# klaboard_schema.net
KiCad netlist of a schematic drawn in EAGLE
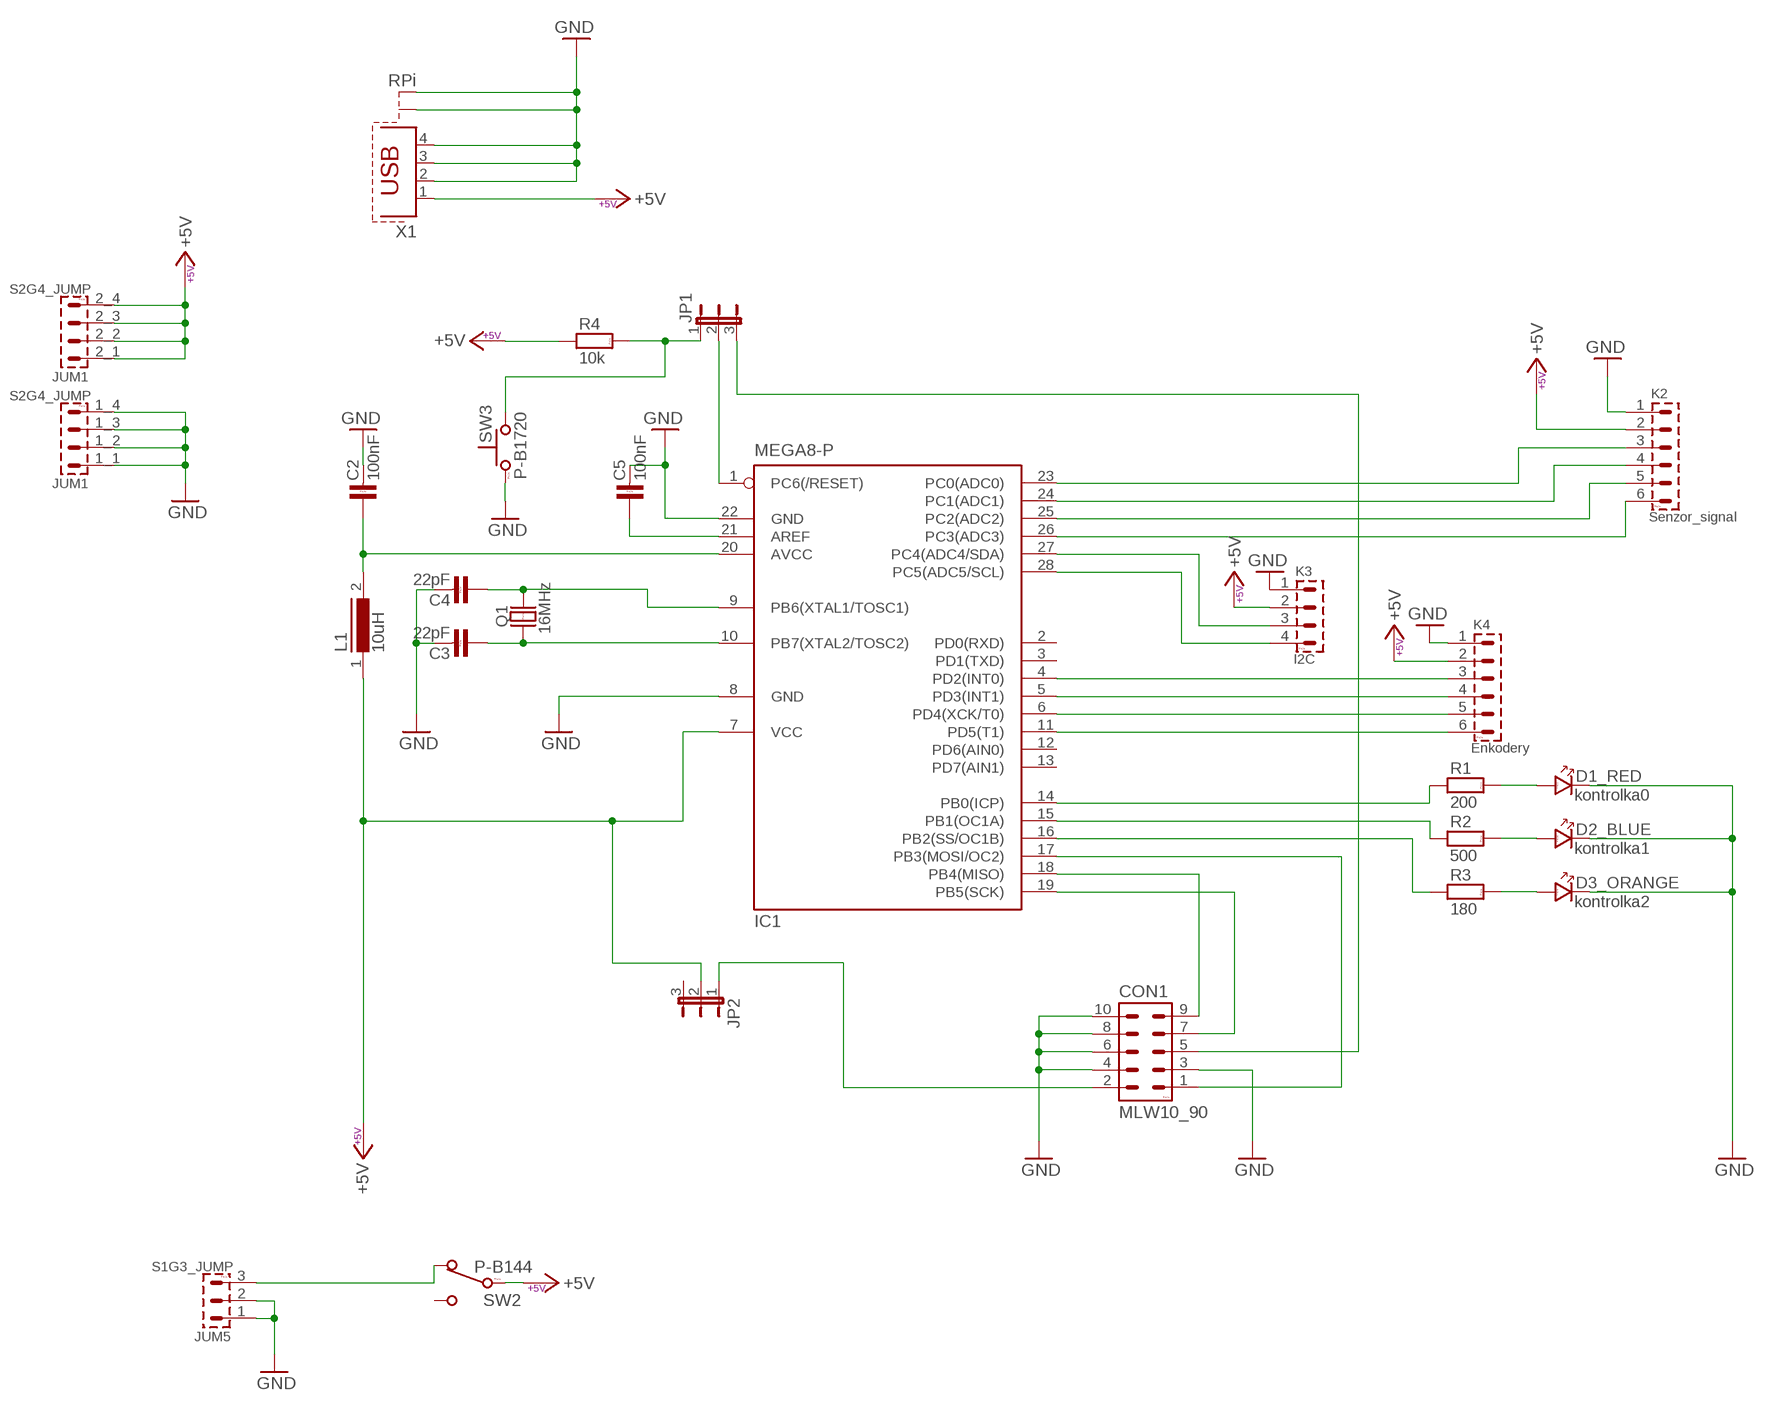
[diagram p0: schematic, sheet 1]

(export (version "E")
  (design (tool "Eeschema 10.0.6"))
  (components
    (comp (ref "C2")
      (value "100nF")
      (footprint "eagle-import:C-7,5")
      (libsource (lib "eagle-import") (part "C-KER_7,5"))
    )
    (comp (ref "C3")
      (value "22pF")
      (footprint "eagle-import:C-7,5")
      (libsource (lib "eagle-import") (part "C-KER_7,5"))
    )
    (comp (ref "C4")
      (value "22pF")
      (footprint "eagle-import:C-7,5")
      (libsource (lib "eagle-import") (part "C-KER_7,5"))
    )
    (comp (ref "C5")
      (value "100nF")
      (footprint "eagle-import:C-7,5")
      (libsource (lib "eagle-import") (part "C-KER_7,5"))
    )
    (comp (ref "CON1")
      (value "MLW10_90")
      (footprint "eagle-import:MLW10A")
      (libsource (lib "eagle-import") (part "MLW10_90°"))
    )
    (comp (ref "D1_RED")
      (value "kontrolka0")
      (footprint "eagle-import:LED_3")
      (libsource (lib "eagle-import") (part "LED_3"))
    )
    (comp (ref "D2_BLUE")
      (value "kontrolka1")
      (footprint "eagle-import:LED_3")
      (libsource (lib "eagle-import") (part "LED_3"))
    )
    (comp (ref "D3_ORANGE")
      (value "kontrolka2")
      (footprint "eagle-import:LED_3")
      (libsource (lib "eagle-import") (part "LED_3"))
    )
    (comp (ref "IC1")
      (value "MEGA8-P")
      (footprint "eagle-import:DIL28-3")
      (libsource (lib "eagle-import") (part "MEGA8-P"))
    )
    (comp (ref "JP1")
      (value "JP2E")
      (footprint "eagle-import:JP2")
      (libsource (lib "eagle-import") (part "JP2E"))
    )
    (comp (ref "JP2")
      (value "JP2E")
      (footprint "eagle-import:JP2")
      (libsource (lib "eagle-import") (part "JP2E"))
    )
    (comp (ref "JUM1")
      (value "S2G4_JUMP")
      (footprint "eagle-import:S2G4_JUM")
      (libsource (lib "eagle-import") (part "S2G4_JUMP"))
    )
    (comp (ref "JUM5")
      (value "S1G3_JUMP")
      (footprint "eagle-import:S1G3_JUM")
      (libsource (lib "eagle-import") (part "S1G3_JUMP"))
    )
    (comp (ref "K2")
      (value "Senzor_signal")
      (footprint "eagle-import:PSH02-06W")
      (libsource (lib "eagle-import") (part "PSH02-06W"))
    )
    (comp (ref "K3")
      (value "I2C")
      (footprint "eagle-import:PSH02-04W")
      (libsource (lib "eagle-import") (part "PSH02-04W"))
    )
    (comp (ref "K4")
      (value "Enkodery")
      (footprint "eagle-import:PSH02-06W")
      (libsource (lib "eagle-import") (part "PSH02-06W"))
    )
    (comp (ref "L1")
      (value "10uH")
      (footprint "eagle-import:SBC10")
      (libsource (lib "eagle-import") (part "SBC10"))
    )
    (comp (ref "Q1")
      (value "16MHz")
      (footprint "eagle-import:HC-49U")
      (libsource (lib "eagle-import") (part "Q_HC-49U"))
    )
    (comp (ref "R1")
      (value "200")
      (footprint "eagle-import:R-12,7")
      (libsource (lib "eagle-import") (part "R_12,7"))
    )
    (comp (ref "R2")
      (value "500")
      (footprint "eagle-import:R-12,7")
      (libsource (lib "eagle-import") (part "R_12,7"))
    )
    (comp (ref "R3")
      (value "180")
      (footprint "eagle-import:R-12,7")
      (libsource (lib "eagle-import") (part "R_12,7"))
    )
    (comp (ref "R4")
      (value "10k")
      (footprint "eagle-import:R-12,7")
      (libsource (lib "eagle-import") (part "R_12,7"))
    )
    (comp (ref "SW2")
      (value "P-B144")
      (footprint "eagle-import:P-B144")
      (libsource (lib "eagle-import") (part "P-B144"))
    )
    (comp (ref "SW3")
      (value "P-B1720")
      (footprint "eagle-import:P-B1720")
      (libsource (lib "eagle-import") (part "P-B1720"))
    )
    (comp (ref "X1")
      (value "RPi")
      (footprint "eagle-import:PN61729-S")
      (libsource (lib "eagle-import") (part "PN61729-S"))
    )
  )
  (nets
    (net (code "1") (name "+5V") (class "Default")
      (node (ref "IC1") (pin "7") (pinfunction "VCC_7") (pintype "power_in"))
      (node (ref "JP2") (pin "2") (pinfunction "2_2") (pintype "passive"))
      (node (ref "JUM1") (pin "2_1") (pinfunction "1_2_1") (pintype "passive"))
      (node (ref "JUM1") (pin "2_2") (pinfunction "2_2_2") (pintype "passive"))
      (node (ref "JUM1") (pin "2_3") (pinfunction "3_2_3") (pintype "passive"))
      (node (ref "JUM1") (pin "2_4") (pinfunction "4_2_4") (pintype "passive"))
      (node (ref "K2") (pin "2") (pinfunction "2_2") (pintype "passive"))
      (node (ref "K3") (pin "2") (pinfunction "2_2") (pintype "passive"))
      (node (ref "K4") (pin "2") (pinfunction "2_2") (pintype "passive"))
      (node (ref "L1") (pin "1") (pinfunction "1_1") (pintype "passive"))
      (node (ref "R4") (pin "1") (pinfunction "1_1") (pintype "passive"))
      (node (ref "SW2") (pin "2") (pinfunction "2-COM_2") (pintype "passive"))
      (node (ref "X1") (pin "1") (pinfunction "1_1") (pintype "passive"))
    )
    (net (code "2") (name "GND") (class "Default")
      (node (ref "C2") (pin "2") (pinfunction "2_2") (pintype "passive"))
      (node (ref "C3") (pin "2") (pinfunction "2_2") (pintype "passive"))
      (node (ref "C4") (pin "2") (pinfunction "2_2") (pintype "passive"))
      (node (ref "C5") (pin "2") (pinfunction "2_2") (pintype "passive"))
      (node (ref "CON1") (pin "10") (pinfunction "10_10") (pintype "passive"))
      (node (ref "CON1") (pin "3") (pinfunction "3_3") (pintype "passive"))
      (node (ref "CON1") (pin "4") (pinfunction "4_4") (pintype "passive"))
      (node (ref "CON1") (pin "6") (pinfunction "6_6") (pintype "passive"))
      (node (ref "CON1") (pin "8") (pinfunction "8_8") (pintype "passive"))
      (node (ref "D1_RED") (pin "K") (pinfunction "K_K") (pintype "passive"))
      (node (ref "D2_BLUE") (pin "K") (pinfunction "K_K") (pintype "passive"))
      (node (ref "D3_ORANGE") (pin "K") (pinfunction "K_K") (pintype "passive"))
      (node (ref "IC1") (pin "22") (pinfunction "GND_22") (pintype "power_in"))
      (node (ref "IC1") (pin "8") (pinfunction "GND_8") (pintype "power_in"))
      (node (ref "JUM1") (pin "1_1") (pinfunction "1_1_1") (pintype "passive"))
      (node (ref "JUM1") (pin "1_2") (pinfunction "2_1_2") (pintype "passive"))
      (node (ref "JUM1") (pin "1_3") (pinfunction "3_1_3") (pintype "passive"))
      (node (ref "JUM1") (pin "1_4") (pinfunction "4_1_4") (pintype "passive"))
      (node (ref "JUM5") (pin "1") (pinfunction "1_1") (pintype "passive"))
      (node (ref "JUM5") (pin "2") (pinfunction "2_2") (pintype "passive"))
      (node (ref "K2") (pin "1") (pinfunction "1_1") (pintype "passive"))
      (node (ref "K3") (pin "1") (pinfunction "1_1") (pintype "passive"))
      (node (ref "K4") (pin "1") (pinfunction "1_1") (pintype "passive"))
      (node (ref "SW3") (pin "1") (pinfunction "1_1") (pintype "passive"))
      (node (ref "X1") (pin "2") (pinfunction "2_2") (pintype "passive"))
      (node (ref "X1") (pin "3") (pinfunction "3_3") (pintype "passive"))
      (node (ref "X1") (pin "4") (pinfunction "4_4") (pintype "passive"))
      (node (ref "X1") (pin "S1") (pinfunction "S1_S1") (pintype "passive"))
      (node (ref "X1") (pin "S2") (pinfunction "S2_S2") (pintype "passive"))
    )
    (net (code "3") (name "Net-(CON1-Pad2)") (class "Default")
      (node (ref "CON1") (pin "2") (pinfunction "2_2") (pintype "passive"))
      (node (ref "JP2") (pin "1") (pinfunction "1_1") (pintype "passive"))
    )
    (net (code "4") (name "Net-(CON1-Pad5)") (class "Default")
      (node (ref "CON1") (pin "5") (pinfunction "5_5") (pintype "passive"))
      (node (ref "JP1") (pin "3") (pinfunction "3_3") (pintype "passive"))
    )
    (net (code "5") (name "Net-(D1_RED-PadA)") (class "Default")
      (node (ref "D1_RED") (pin "A") (pinfunction "A_A") (pintype "passive"))
      (node (ref "R1") (pin "2") (pinfunction "2_2") (pintype "passive"))
    )
    (net (code "6") (name "Net-(D2_BLUE-PadA)") (class "Default")
      (node (ref "D2_BLUE") (pin "A") (pinfunction "A_A") (pintype "passive"))
      (node (ref "R2") (pin "2") (pinfunction "2_2") (pintype "passive"))
    )
    (net (code "7") (name "Net-(D3_ORANGE-PadA)") (class "Default")
      (node (ref "D3_ORANGE") (pin "A") (pinfunction "A_A") (pintype "passive"))
      (node (ref "R3") (pin "2") (pinfunction "2_2") (pintype "passive"))
    )
    (net (code "8") (name "Net-(IC1-AREF)") (class "Default")
      (node (ref "C5") (pin "1") (pinfunction "1_1") (pintype "passive"))
      (node (ref "IC1") (pin "21") (pinfunction "AREF_21") (pintype "passive"))
    )
    (net (code "9") (name "Net-(IC1-AVCC)") (class "Default")
      (node (ref "C2") (pin "1") (pinfunction "1_1") (pintype "passive"))
      (node (ref "IC1") (pin "20") (pinfunction "AVCC_20") (pintype "power_in"))
      (node (ref "L1") (pin "2") (pinfunction "2_2") (pintype "passive"))
    )
    (net (code "10") (name "Net-(IC1-PB0(ICP))") (class "Default")
      (node (ref "IC1") (pin "14") (pinfunction "PB0(ICP)_14") (pintype "bidirectional"))
      (node (ref "R1") (pin "1") (pinfunction "1_1") (pintype "passive"))
    )
    (net (code "11") (name "Net-(IC1-PB1(OC1A))") (class "Default")
      (node (ref "IC1") (pin "15") (pinfunction "PB1(OC1A)_15") (pintype "bidirectional"))
      (node (ref "R2") (pin "1") (pinfunction "1_1") (pintype "passive"))
    )
    (net (code "12") (name "Net-(IC1-PB2(SS{slash}OC1B))") (class "Default")
      (node (ref "IC1") (pin "16") (pinfunction "PB2(SS/OC1B)_16") (pintype "bidirectional"))
      (node (ref "R3") (pin "1") (pinfunction "1_1") (pintype "passive"))
    )
    (net (code "13") (name "Net-(IC1-PB3(MOSI{slash}OC2))") (class "Default")
      (node (ref "CON1") (pin "1") (pinfunction "1_1") (pintype "passive"))
      (node (ref "IC1") (pin "17") (pinfunction "PB3(MOSI/OC2)_17") (pintype "bidirectional"))
    )
    (net (code "14") (name "Net-(IC1-PB4(MISO))") (class "Default")
      (node (ref "CON1") (pin "9") (pinfunction "9_9") (pintype "passive"))
      (node (ref "IC1") (pin "18") (pinfunction "PB4(MISO)_18") (pintype "bidirectional"))
    )
    (net (code "15") (name "Net-(IC1-PB5(SCK))") (class "Default")
      (node (ref "CON1") (pin "7") (pinfunction "7_7") (pintype "passive"))
      (node (ref "IC1") (pin "19") (pinfunction "PB5(SCK)_19") (pintype "bidirectional"))
    )
    (net (code "16") (name "Net-(IC1-PB6(XTAL1{slash}TOSC1))") (class "Default")
      (node (ref "C4") (pin "1") (pinfunction "1_1") (pintype "passive"))
      (node (ref "IC1") (pin "9") (pinfunction "PB6(XTAL1/TOSC1)_9") (pintype "bidirectional"))
      (node (ref "Q1") (pin "2") (pinfunction "2_2") (pintype "passive"))
    )
    (net (code "17") (name "Net-(IC1-PB7(XTAL2{slash}TOSC2))") (class "Default")
      (node (ref "C3") (pin "1") (pinfunction "1_1") (pintype "passive"))
      (node (ref "IC1") (pin "10") (pinfunction "PB7(XTAL2/TOSC2)_10") (pintype "bidirectional"))
      (node (ref "Q1") (pin "1") (pinfunction "1_1") (pintype "passive"))
    )
    (net (code "18") (name "Net-(IC1-PC0(ADC0))") (class "Default")
      (node (ref "IC1") (pin "23") (pinfunction "PC0(ADC0)_23") (pintype "bidirectional"))
      (node (ref "K2") (pin "3") (pinfunction "3_3") (pintype "passive"))
    )
    (net (code "19") (name "Net-(IC1-PC1(ADC1))") (class "Default")
      (node (ref "IC1") (pin "24") (pinfunction "PC1(ADC1)_24") (pintype "bidirectional"))
      (node (ref "K2") (pin "4") (pinfunction "4_4") (pintype "passive"))
    )
    (net (code "20") (name "Net-(IC1-PC2(ADC2))") (class "Default")
      (node (ref "IC1") (pin "25") (pinfunction "PC2(ADC2)_25") (pintype "bidirectional"))
      (node (ref "K2") (pin "5") (pinfunction "5_5") (pintype "passive"))
    )
    (net (code "21") (name "Net-(IC1-PC3(ADC3))") (class "Default")
      (node (ref "IC1") (pin "26") (pinfunction "PC3(ADC3)_26") (pintype "bidirectional"))
      (node (ref "K2") (pin "6") (pinfunction "6_6") (pintype "passive"))
    )
    (net (code "22") (name "Net-(IC1-PC4(ADC4{slash}SDA))") (class "Default")
      (node (ref "IC1") (pin "27") (pinfunction "PC4(ADC4/SDA)_27") (pintype "bidirectional"))
      (node (ref "K3") (pin "3") (pinfunction "3_3") (pintype "passive"))
    )
    (net (code "23") (name "Net-(IC1-PC5(ADC5{slash}SCL))") (class "Default")
      (node (ref "IC1") (pin "28") (pinfunction "PC5(ADC5/SCL)_28") (pintype "bidirectional"))
      (node (ref "K3") (pin "4") (pinfunction "4_4") (pintype "passive"))
    )
    (net (code "24") (name "Net-(IC1-PC6({slash}RESET))") (class "Default")
      (node (ref "IC1") (pin "1") (pinfunction "PC6(/RESET)_1") (pintype "bidirectional"))
      (node (ref "JP1") (pin "2") (pinfunction "2_2") (pintype "passive"))
    )
    (net (code "25") (name "Net-(IC1-PD2(INT0))") (class "Default")
      (node (ref "IC1") (pin "4") (pinfunction "PD2(INT0)_4") (pintype "bidirectional"))
      (node (ref "K4") (pin "3") (pinfunction "3_3") (pintype "passive"))
    )
    (net (code "26") (name "Net-(IC1-PD3(INT1))") (class "Default")
      (node (ref "IC1") (pin "5") (pinfunction "PD3(INT1)_5") (pintype "bidirectional"))
      (node (ref "K4") (pin "4") (pinfunction "4_4") (pintype "passive"))
    )
    (net (code "27") (name "Net-(IC1-PD4(XCK{slash}T0))") (class "Default")
      (node (ref "IC1") (pin "6") (pinfunction "PD4(XCK/T0)_6") (pintype "bidirectional"))
      (node (ref "K4") (pin "5") (pinfunction "5_5") (pintype "passive"))
    )
    (net (code "28") (name "Net-(IC1-PD5(T1))") (class "Default")
      (node (ref "IC1") (pin "11") (pinfunction "PD5(T1)_11") (pintype "bidirectional"))
      (node (ref "K4") (pin "6") (pinfunction "6_6") (pintype "passive"))
    )
    (net (code "29") (name "Net-(JP1-Pad1)") (class "Default")
      (node (ref "JP1") (pin "1") (pinfunction "1_1") (pintype "passive"))
      (node (ref "R4") (pin "2") (pinfunction "2_2") (pintype "passive"))
      (node (ref "SW3") (pin "2") (pinfunction "2_2") (pintype "passive"))
    )
    (net (code "30") (name "Net-(SW2-3-NC)") (class "Default")
      (node (ref "JUM5") (pin "3") (pinfunction "3_3") (pintype "passive"))
      (node (ref "SW2") (pin "3") (pinfunction "3-NC_3") (pintype "passive"))
    )
    (net (code "31") (name "unconnected-(IC1-PD0(RXD)-Pad2)") (class "Default")
      (node (ref "IC1") (pin "2") (pinfunction "PD0(RXD)_2") (pintype "bidirectional"))
    )
    (net (code "32") (name "unconnected-(IC1-PD1(TXD)-Pad3)") (class "Default")
      (node (ref "IC1") (pin "3") (pinfunction "PD1(TXD)_3") (pintype "bidirectional"))
    )
    (net (code "33") (name "unconnected-(IC1-PD6(AIN0)-Pad12)") (class "Default")
      (node (ref "IC1") (pin "12") (pinfunction "PD6(AIN0)_12") (pintype "bidirectional"))
    )
    (net (code "34") (name "unconnected-(IC1-PD7(AIN1)-Pad13)") (class "Default")
      (node (ref "IC1") (pin "13") (pinfunction "PD7(AIN1)_13") (pintype "bidirectional"))
    )
    (net (code "35") (name "unconnected-(JP2-Pad3)") (class "Default")
      (node (ref "JP2") (pin "3") (pinfunction "3_3") (pintype "passive"))
    )
    (net (code "36") (name "unconnected-(SW2-1-NO-Pad1)") (class "Default")
      (node (ref "SW2") (pin "1") (pinfunction "1-NO_1") (pintype "passive"))
    )
    (net (code "37") (name "unconnected-(SW3-1A-Pad3)") (class "Default")
      (node (ref "SW3") (pin "3") (pinfunction "1A_3") (pintype "passive"))
    )
    (net (code "38") (name "unconnected-(SW3-2A-Pad4)") (class "Default")
      (node (ref "SW3") (pin "4") (pinfunction "2A_4") (pintype "passive"))
    )
  )
)
